# avr_7seg_charset.net
KiCad netlist of a schematic drawn in EAGLE
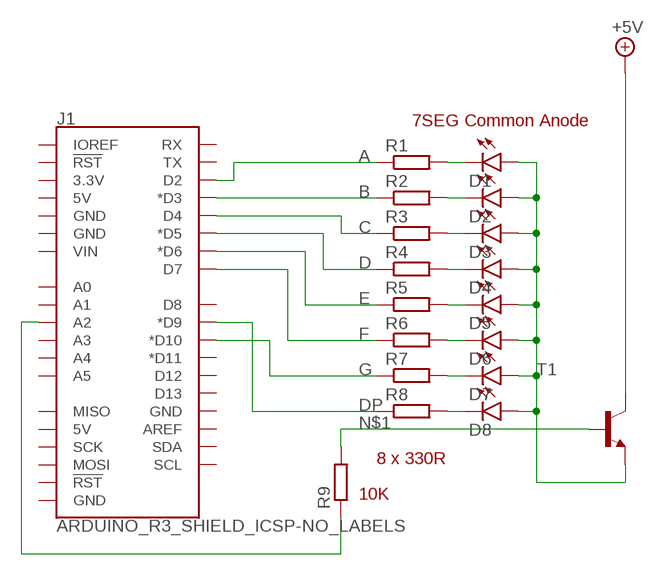
[diagram p0: schematic, sheet 1]

(export (version "E")
  (design (tool "Eeschema 10.0.6"))
  (components
    (comp (ref "D1")
      (value "LED3MM")
      (footprint "eagle-import:LED3MM")
      (libsource (lib "eagle-import") (part "LED3MM"))
    )
    (comp (ref "D2")
      (value "LED3MM")
      (footprint "eagle-import:LED3MM")
      (libsource (lib "eagle-import") (part "LED3MM"))
    )
    (comp (ref "D3")
      (value "LED3MM")
      (footprint "eagle-import:LED3MM")
      (libsource (lib "eagle-import") (part "LED3MM"))
    )
    (comp (ref "D4")
      (value "LED3MM")
      (footprint "eagle-import:LED3MM")
      (libsource (lib "eagle-import") (part "LED3MM"))
    )
    (comp (ref "D5")
      (value "LED3MM")
      (footprint "eagle-import:LED3MM")
      (libsource (lib "eagle-import") (part "LED3MM"))
    )
    (comp (ref "D6")
      (value "LED3MM")
      (footprint "eagle-import:LED3MM")
      (libsource (lib "eagle-import") (part "LED3MM"))
    )
    (comp (ref "D7")
      (value "LED3MM")
      (footprint "eagle-import:LED3MM")
      (libsource (lib "eagle-import") (part "LED3MM"))
    )
    (comp (ref "D8")
      (value "LED3MM")
      (footprint "eagle-import:LED3MM")
      (libsource (lib "eagle-import") (part "LED3MM"))
    )
    (comp (ref "J1")
      (value "ARDUINO_R3_SHIELD_ICSP-NO_LABELS")
      (footprint "eagle-import:UNO_R3_SHIELD_ICSP_NOLABELS")
      (libsource (lib "eagle-import") (part "ARDUINO_R3_SHIELD_ICSP-NO_LABELS"))
    )
    (comp (ref "R1")
      (value "R-EU_0207/7")
      (footprint "eagle-import:0207_7")
      (libsource (lib "eagle-import") (part "R-EU_0207/7"))
    )
    (comp (ref "R2")
      (value "R-EU_0207/7")
      (footprint "eagle-import:0207_7")
      (libsource (lib "eagle-import") (part "R-EU_0207/7"))
    )
    (comp (ref "R3")
      (value "R-EU_0207/7")
      (footprint "eagle-import:0207_7")
      (libsource (lib "eagle-import") (part "R-EU_0207/7"))
    )
    (comp (ref "R4")
      (value "R-EU_0207/7")
      (footprint "eagle-import:0207_7")
      (libsource (lib "eagle-import") (part "R-EU_0207/7"))
    )
    (comp (ref "R5")
      (value "R-EU_0207/7")
      (footprint "eagle-import:0207_7")
      (libsource (lib "eagle-import") (part "R-EU_0207/7"))
    )
    (comp (ref "R6")
      (value "R-EU_0207/7")
      (footprint "eagle-import:0207_7")
      (libsource (lib "eagle-import") (part "R-EU_0207/7"))
    )
    (comp (ref "R7")
      (value "R-EU_0207/7")
      (footprint "eagle-import:0207_7")
      (libsource (lib "eagle-import") (part "R-EU_0207/7"))
    )
    (comp (ref "R8")
      (value "R-EU_0207/7")
      (footprint "eagle-import:0207_7")
      (libsource (lib "eagle-import") (part "R-EU_0207/7"))
    )
    (comp (ref "R9")
      (value "R-EU_0207/7")
      (footprint "eagle-import:0207_7")
      (libsource (lib "eagle-import") (part "R-EU_0207/7"))
    )
    (comp (ref "T1")
      (value "-NPN-TO92-EBC")
      (footprint "eagle-import:TO92-EBC")
      (libsource (lib "eagle-import") (part "-NPN-TO92-EBC"))
    )
  )
  (nets
    (net (code "1") (name "+5V") (class "Default")
      (node (ref "T1") (pin "C") (pinfunction "C_C") (pintype "passive"))
    )
    (net (code "2") (name "/A") (class "Default")
      (node (ref "J1") (pin "D2") (pinfunction "D2_D2") (pintype "bidirectional"))
      (node (ref "R1") (pin "1") (pinfunction "1_1") (pintype "passive"))
    )
    (net (code "3") (name "/B") (class "Default")
      (node (ref "J1") (pin "D3") (pinfunction "*D3_D3") (pintype "bidirectional"))
      (node (ref "R2") (pin "1") (pinfunction "1_1") (pintype "passive"))
    )
    (net (code "4") (name "/C") (class "Default")
      (node (ref "J1") (pin "D4") (pinfunction "D4_D4") (pintype "bidirectional"))
      (node (ref "R3") (pin "1") (pinfunction "1_1") (pintype "passive"))
    )
    (net (code "5") (name "/D") (class "Default")
      (node (ref "J1") (pin "D5") (pinfunction "*D5_D5") (pintype "bidirectional"))
      (node (ref "R4") (pin "1") (pinfunction "1_1") (pintype "passive"))
    )
    (net (code "6") (name "/DP") (class "Default")
      (node (ref "J1") (pin "D9") (pinfunction "*D9_D9") (pintype "bidirectional"))
      (node (ref "R8") (pin "1") (pinfunction "1_1") (pintype "passive"))
    )
    (net (code "7") (name "/E") (class "Default")
      (node (ref "J1") (pin "D6") (pinfunction "*D6_D6") (pintype "bidirectional"))
      (node (ref "R5") (pin "1") (pinfunction "1_1") (pintype "passive"))
    )
    (net (code "8") (name "/F") (class "Default")
      (node (ref "J1") (pin "D7") (pinfunction "D7_D7") (pintype "bidirectional"))
      (node (ref "R6") (pin "1") (pinfunction "1_1") (pintype "passive"))
    )
    (net (code "9") (name "/G") (class "Default")
      (node (ref "J1") (pin "D10") (pinfunction "*D10_D10") (pintype "bidirectional"))
      (node (ref "R7") (pin "1") (pinfunction "1_1") (pintype "passive"))
    )
    (net (code "10") (name "/N$1") (class "Default")
      (node (ref "R9") (pin "2") (pinfunction "2_2") (pintype "passive"))
      (node (ref "T1") (pin "B") (pinfunction "B_B") (pintype "passive"))
    )
    (net (code "11") (name "Net-(D1-C)") (class "Default")
      (node (ref "D1") (pin "K") (pinfunction "C_K") (pintype "passive"))
      (node (ref "R1") (pin "2") (pinfunction "2_2") (pintype "passive"))
    )
    (net (code "12") (name "Net-(D1-PadA)") (class "Default")
      (node (ref "D1") (pin "A") (pinfunction "A_A") (pintype "passive"))
      (node (ref "D2") (pin "A") (pinfunction "A_A") (pintype "passive"))
      (node (ref "D3") (pin "A") (pinfunction "A_A") (pintype "passive"))
      (node (ref "D4") (pin "A") (pinfunction "A_A") (pintype "passive"))
      (node (ref "D5") (pin "A") (pinfunction "A_A") (pintype "passive"))
      (node (ref "D6") (pin "A") (pinfunction "A_A") (pintype "passive"))
      (node (ref "D7") (pin "A") (pinfunction "A_A") (pintype "passive"))
      (node (ref "D8") (pin "A") (pinfunction "A_A") (pintype "passive"))
      (node (ref "T1") (pin "E") (pinfunction "E_E") (pintype "passive"))
    )
    (net (code "13") (name "Net-(D2-C)") (class "Default")
      (node (ref "D2") (pin "K") (pinfunction "C_K") (pintype "passive"))
      (node (ref "R2") (pin "2") (pinfunction "2_2") (pintype "passive"))
    )
    (net (code "14") (name "Net-(D3-C)") (class "Default")
      (node (ref "D3") (pin "K") (pinfunction "C_K") (pintype "passive"))
      (node (ref "R3") (pin "2") (pinfunction "2_2") (pintype "passive"))
    )
    (net (code "15") (name "Net-(D4-C)") (class "Default")
      (node (ref "D4") (pin "K") (pinfunction "C_K") (pintype "passive"))
      (node (ref "R4") (pin "2") (pinfunction "2_2") (pintype "passive"))
    )
    (net (code "16") (name "Net-(D5-C)") (class "Default")
      (node (ref "D5") (pin "K") (pinfunction "C_K") (pintype "passive"))
      (node (ref "R5") (pin "2") (pinfunction "2_2") (pintype "passive"))
    )
    (net (code "17") (name "Net-(D6-C)") (class "Default")
      (node (ref "D6") (pin "K") (pinfunction "C_K") (pintype "passive"))
      (node (ref "R6") (pin "2") (pinfunction "2_2") (pintype "passive"))
    )
    (net (code "18") (name "Net-(D7-C)") (class "Default")
      (node (ref "D7") (pin "K") (pinfunction "C_K") (pintype "passive"))
      (node (ref "R7") (pin "2") (pinfunction "2_2") (pintype "passive"))
    )
    (net (code "19") (name "Net-(D8-C)") (class "Default")
      (node (ref "D8") (pin "K") (pinfunction "C_K") (pintype "passive"))
      (node (ref "R8") (pin "2") (pinfunction "2_2") (pintype "passive"))
    )
    (net (code "20") (name "Net-(J1-PadA2)") (class "Default")
      (node (ref "J1") (pin "A2") (pinfunction "A2_A2") (pintype "bidirectional"))
      (node (ref "R9") (pin "1") (pinfunction "1_1") (pintype "passive"))
    )
    (net (code "21") (name "unconnected-(J1-*D11-PadD11)") (class "Default")
      (node (ref "J1") (pin "D11") (pinfunction "*D11_D11") (pintype "bidirectional"))
    )
    (net (code "22") (name "unconnected-(J1-5V-Pad5V_ICSP)") (class "Default")
      (node (ref "J1") (pin "5V_ICSP") (pinfunction "5V_5V_ICSP") (pintype "bidirectional"))
    )
    (net (code "23") (name "unconnected-(J1-GND-PadGND@0)") (class "Default")
      (node (ref "J1") (pin "GND@0") (pinfunction "GND_GND@0") (pintype "bidirectional"))
    )
    (net (code "24") (name "unconnected-(J1-GND-PadGND@1)") (class "Default")
      (node (ref "J1") (pin "GND@1") (pinfunction "GND_GND@1") (pintype "bidirectional"))
    )
    (net (code "25") (name "unconnected-(J1-GND-PadGND@2)") (class "Default")
      (node (ref "J1") (pin "GND@2") (pinfunction "GND_GND@2") (pintype "bidirectional"))
    )
    (net (code "26") (name "unconnected-(J1-GND-PadGND_ICSP)") (class "Default")
      (node (ref "J1") (pin "GND_ICSP") (pinfunction "GND_GND_ICSP") (pintype "bidirectional"))
    )
    (net (code "27") (name "unconnected-(J1-Pad3.3V)") (class "Default")
      (node (ref "J1") (pin "3.3V") (pinfunction "3.3V_3.3V") (pintype "bidirectional"))
    )
    (net (code "28") (name "unconnected-(J1-Pad5V)") (class "Default")
      (node (ref "J1") (pin "5V") (pinfunction "5V_5V") (pintype "bidirectional"))
    )
    (net (code "29") (name "unconnected-(J1-PadA0)") (class "Default")
      (node (ref "J1") (pin "A0") (pinfunction "A0_A0") (pintype "bidirectional"))
    )
    (net (code "30") (name "unconnected-(J1-PadA1)") (class "Default")
      (node (ref "J1") (pin "A1") (pinfunction "A1_A1") (pintype "bidirectional"))
    )
    (net (code "31") (name "unconnected-(J1-PadA3)") (class "Default")
      (node (ref "J1") (pin "A3") (pinfunction "A3_A3") (pintype "bidirectional"))
    )
    (net (code "32") (name "unconnected-(J1-PadA4)") (class "Default")
      (node (ref "J1") (pin "A4") (pinfunction "A4_A4") (pintype "bidirectional"))
    )
    (net (code "33") (name "unconnected-(J1-PadA5)") (class "Default")
      (node (ref "J1") (pin "A5") (pinfunction "A5_A5") (pintype "bidirectional"))
    )
    (net (code "34") (name "unconnected-(J1-PadAREF)") (class "Default")
      (node (ref "J1") (pin "AREF") (pinfunction "AREF_AREF") (pintype "bidirectional"))
    )
    (net (code "35") (name "unconnected-(J1-PadD8)") (class "Default")
      (node (ref "J1") (pin "D8") (pinfunction "D8_D8") (pintype "bidirectional"))
    )
    (net (code "36") (name "unconnected-(J1-PadD12)") (class "Default")
      (node (ref "J1") (pin "D12") (pinfunction "D12_D12") (pintype "bidirectional"))
    )
    (net (code "37") (name "unconnected-(J1-PadD13)") (class "Default")
      (node (ref "J1") (pin "D13") (pinfunction "D13_D13") (pintype "bidirectional"))
    )
    (net (code "38") (name "unconnected-(J1-PadIOREF)") (class "Default")
      (node (ref "J1") (pin "IOREF") (pinfunction "IOREF_IOREF") (pintype "bidirectional"))
    )
    (net (code "39") (name "unconnected-(J1-PadMISO)") (class "Default")
      (node (ref "J1") (pin "MISO") (pinfunction "MISO_MISO") (pintype "bidirectional"))
    )
    (net (code "40") (name "unconnected-(J1-PadMOSI)") (class "Default")
      (node (ref "J1") (pin "MOSI") (pinfunction "MOSI_MOSI") (pintype "bidirectional"))
    )
    (net (code "41") (name "unconnected-(J1-PadRX)") (class "Default")
      (node (ref "J1") (pin "RX") (pinfunction "RX_RX") (pintype "bidirectional"))
    )
    (net (code "42") (name "unconnected-(J1-PadSCK)") (class "Default")
      (node (ref "J1") (pin "SCK") (pinfunction "SCK_SCK") (pintype "bidirectional"))
    )
    (net (code "43") (name "unconnected-(J1-PadSCL)") (class "Default")
      (node (ref "J1") (pin "SCL") (pinfunction "SCL_SCL") (pintype "bidirectional"))
    )
    (net (code "44") (name "unconnected-(J1-PadSDA)") (class "Default")
      (node (ref "J1") (pin "SDA") (pinfunction "SDA_SDA") (pintype "bidirectional"))
    )
    (net (code "45") (name "unconnected-(J1-PadTX)") (class "Default")
      (node (ref "J1") (pin "TX") (pinfunction "TX_TX") (pintype "bidirectional"))
    )
    (net (code "46") (name "unconnected-(J1-PadVIN)") (class "Default")
      (node (ref "J1") (pin "VIN") (pinfunction "VIN_VIN") (pintype "bidirectional"))
    )
    (net (code "47") (name "unconnected-(J1-~{RST}-PadRES)") (class "Default")
      (node (ref "J1") (pin "RES") (pinfunction "~{RST}_RES") (pintype "bidirectional"))
    )
    (net (code "48") (name "unconnected-(J1-~{RST}-PadRST_ICSP)") (class "Default")
      (node (ref "J1") (pin "RST_ICSP") (pinfunction "~{RST}_RST_ICSP") (pintype "bidirectional"))
    )
  )
)
